# Power.net
KiCad netlist of a schematic drawn in Altium Designer
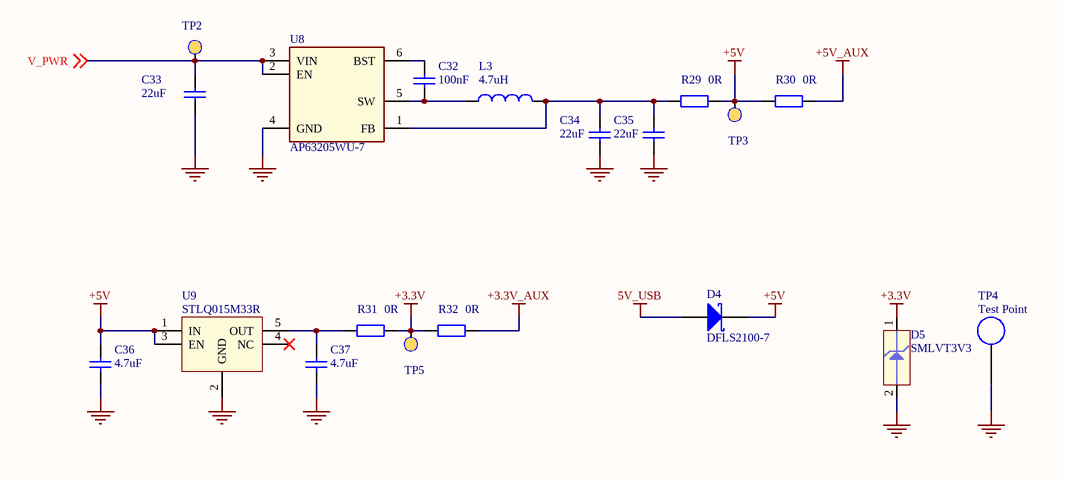
[diagram p0: Power.SchDoc]

(export (version "E")
  (design (tool "Eeschema 10.0.6"))
  (components
    (comp (ref "C32")
      (value "100nF")
      (footprint "C0402")
      (description "Capacitor ceramic")
      (fields
        (field (name "MANUFACTURER") "TDK Corporation")
        (field (name "MANUFACTURER PART NO.") "CGA2B3X7R1V104K050BB")
      )
      (libsource (lib "Miscellaneous Devices") (part "Cap Semi"))
    )
    (comp (ref "C33")
      (value "22uF")
      (footprint "C1210")
      (description "Capacitor ceramic")
      (fields
        (field (name "MANUFACTURER") "Taiyo Yuden")
        (field (name "MANUFACTURER PART NO.") "GMK325BJ226MM-P")
      )
      (libsource (lib "Miscellaneous Devices") (part "Cap Semi"))
    )
    (comp (ref "C34")
      (value "22uF")
      (footprint "C1210")
      (description "Capacitor ceramic")
      (fields
        (field (name "MANUFACTURER") "Taiyo Yuden")
        (field (name "MANUFACTURER PART NO.") "GMK325BJ226MM-P")
      )
      (libsource (lib "Miscellaneous Devices") (part "Cap Semi"))
    )
    (comp (ref "C35")
      (value "22uF")
      (footprint "C1210")
      (description "Capacitor ceramic")
      (fields
        (field (name "MANUFACTURER") "Taiyo Yuden")
        (field (name "MANUFACTURER PART NO.") "GMK325BJ226MM-P")
      )
      (libsource (lib "Miscellaneous Devices") (part "Cap Semi"))
    )
    (comp (ref "C36")
      (value "4.7uF")
      (footprint "C0805")
      (description "Capacitor ceramic")
      (fields
        (field (name "MANUFACTURER") "Murata Electronics")
        (field (name "MANUFACTURER PART NO.") "GRM219R6YA475KA73D")
      )
      (libsource (lib "Miscellaneous Devices") (part "Cap Semi"))
    )
    (comp (ref "C37")
      (value "4.7uF")
      (footprint "C0805")
      (description "Capacitor ceramic")
      (fields
        (field (name "MANUFACTURER") "Murata Electronics")
        (field (name "MANUFACTURER PART NO.") "GRM219R6YA475KA73D")
      )
      (libsource (lib "Miscellaneous Devices") (part "Cap Semi"))
    )
    (comp (ref "D4")
      (value "DFLS2100-7")
      (footprint "PowerDI123")
      (description "Schottky Diode")
      (fields (field (name "MANUFACTURER") "Diodes Incorporated"))
      (libsource (lib "Miscellaneous Devices") (part "D Schottky"))
    )
    (comp (ref "D5")
      (value "SMLVT3V3")
      (footprint "DO-214AA")
      (description "ESD Diode Symbol")
      (fields (field (name "MANUFACTURER") "STMicroelectronics"))
      (libsource (lib "ESD_Diode") (part "ESD_Diode"))
    )
    (comp (ref "L3")
      (value "4.7uH")
      (footprint "LQH3NP")
      (description "Inductor")
      (fields
        (field (name "MANUFACTURER") "Murata Electronics")
        (field (name "MANUFACTURER PART NO.") "LQH3NPN4R7MMEL")
      )
      (libsource (lib "Miscellaneous Devices") (part "Inductor"))
    )
    (comp (ref "R29")
      (value "0R")
      (footprint "R1206")
      (description "Resistor")
      (fields (field (name "MANUFACTURER") "Yageo") (field (name "MANUFACTURER PART NO.") "RC1206JR-070RL"))
      (libsource (lib "Miscellaneous Devices") (part "Res2"))
    )
    (comp (ref "R30")
      (value "0R")
      (footprint "R1206")
      (description "Resistor")
      (fields (field (name "MANUFACTURER") "Yageo") (field (name "MANUFACTURER PART NO.") "RC1206JR-070RL"))
      (libsource (lib "Miscellaneous Devices") (part "Res2"))
    )
    (comp (ref "R31")
      (value "0R")
      (footprint "R1206")
      (description "Resistor")
      (fields (field (name "MANUFACTURER") "Yageo") (field (name "MANUFACTURER PART NO.") "RC1206JR-070RL"))
      (libsource (lib "Miscellaneous Devices") (part "Res2"))
    )
    (comp (ref "R32")
      (value "0R")
      (footprint "R1206")
      (description "Resistor")
      (fields (field (name "MANUFACTURER") "Yageo") (field (name "MANUFACTURER PART NO.") "RC1206JR-070RL"))
      (libsource (lib "Miscellaneous Devices") (part "Res2"))
    )
    (comp (ref "TP2")
      (value "Test_Point")
      (footprint "TEST_POINT")
      (description "Test Point")
      (libsource (lib "Test Point") (part "Test_Point"))
    )
    (comp (ref "TP3")
      (value "Test_Point")
      (footprint "TEST_POINT")
      (description "Test Point")
      (libsource (lib "Test Point") (part "Test_Point"))
    )
    (comp (ref "TP4")
      (value "Test Point")
      (footprint "5019_keystone")
      (description "SMD Test Point")
      (fields
        (field (name "MANUFACTURER") "Keystone Electronics")
        (field (name "MANUFACTURER PART NO.") "5019")
      )
      (libsource (lib "test_point") (part "5019"))
    )
    (comp (ref "TP5")
      (value "Test_Point")
      (footprint "TEST_POINT")
      (description "Test Point")
      (libsource (lib "Test Point") (part "Test_Point"))
    )
    (comp (ref "U8")
      (value "AP63205WU-7")
      (footprint "SOT23-6_custom")
      (description "SYNCHRONOUS BUCK WITH ENHANCED EMI REDUCTION")
      (fields (field (name "MANUFACTURER") "Diodes Incorporated"))
      (libsource (lib "AP63205WU-7") (part "AP63205WU-7"))
    )
    (comp (ref "U9")
      (value "STLQ015M33R")
      (footprint "SOT23-5L")
      (description "Ultra low quiescent current linear voltage regulator")
      (fields (field (name "MANUFACTURER") "STMicroelectronics"))
      (libsource (lib "STLQ015M33R") (part "STLQ015M33R"))
    )
  )
  (nets
    (net (code "1") (name "+3.3V") (class "Default")
      (node (ref "D5") (pin "1") (pinfunction "PIN1_1") (pintype "passive"))
      (node (ref "R31") (pin "1") (pinfunction "1_1") (pintype "passive"))
      (node (ref "R32") (pin "2") (pinfunction "2_2") (pintype "passive"))
      (node (ref "TP5") (pin "0") (pinfunction "0_0") (pintype "passive"))
    )
    (net (code "2") (name "+3.3V_AUX") (class "Default")
      (node (ref "R32") (pin "1") (pinfunction "1_1") (pintype "passive"))
    )
    (net (code "3") (name "+5V") (class "Default")
      (node (ref "C36") (pin "2") (pinfunction "2_2") (pintype "passive"))
      (node (ref "D4") (pin "2") (pinfunction "K_2") (pintype "passive"))
      (node (ref "R29") (pin "1") (pinfunction "1_1") (pintype "passive"))
      (node (ref "R30") (pin "2") (pinfunction "2_2") (pintype "passive"))
      (node (ref "TP3") (pin "0") (pinfunction "0_0") (pintype "passive"))
      (node (ref "U9") (pin "1") (pinfunction "IN_1") (pintype "passive"))
      (node (ref "U9") (pin "3") (pinfunction "EN_3") (pintype "passive"))
    )
    (net (code "4") (name "+5V_AUX") (class "Default")
      (node (ref "R30") (pin "1") (pinfunction "1_1") (pintype "passive"))
    )
    (net (code "5") (name "5V_USB") (class "Default")
      (node (ref "D4") (pin "1") (pinfunction "A_1") (pintype "passive"))
    )
    (net (code "6") (name "GND") (class "Default")
      (node (ref "C33") (pin "1") (pinfunction "1_1") (pintype "passive"))
      (node (ref "C34") (pin "1") (pinfunction "1_1") (pintype "passive"))
      (node (ref "C35") (pin "1") (pinfunction "1_1") (pintype "passive"))
      (node (ref "C36") (pin "1") (pinfunction "1_1") (pintype "passive"))
      (node (ref "C37") (pin "1") (pinfunction "1_1") (pintype "passive"))
      (node (ref "D5") (pin "2") (pinfunction "PIN2_2") (pintype "passive"))
      (node (ref "TP4") (pin "1") (pinfunction "1_1") (pintype "passive"))
      (node (ref "U8") (pin "4") (pinfunction "GND_4") (pintype "passive"))
      (node (ref "U9") (pin "2") (pinfunction "GND_2") (pintype "passive"))
    )
    (net (code "7") (name "Net-(U8-BST)") (class "Default")
      (node (ref "C32") (pin "2") (pinfunction "2_2") (pintype "passive"))
      (node (ref "U8") (pin "6") (pinfunction "BST_6") (pintype "passive"))
    )
    (net (code "8") (name "Net-(U8-FB)") (class "Default")
      (node (ref "C34") (pin "2") (pinfunction "2_2") (pintype "passive"))
      (node (ref "C35") (pin "2") (pinfunction "2_2") (pintype "passive"))
      (node (ref "L3") (pin "2") (pinfunction "2_2") (pintype "passive"))
      (node (ref "R29") (pin "2") (pinfunction "2_2") (pintype "passive"))
      (node (ref "U8") (pin "1") (pinfunction "FB_1") (pintype "passive"))
    )
    (net (code "9") (name "Net-(U8-SW)") (class "Default")
      (node (ref "C32") (pin "1") (pinfunction "1_1") (pintype "passive"))
      (node (ref "L3") (pin "1") (pinfunction "1_1") (pintype "passive"))
      (node (ref "U8") (pin "5") (pinfunction "SW_5") (pintype "passive"))
    )
    (net (code "10") (name "Net-(U9-OUT)") (class "Default")
      (node (ref "C37") (pin "2") (pinfunction "2_2") (pintype "passive"))
      (node (ref "R31") (pin "2") (pinfunction "2_2") (pintype "passive"))
      (node (ref "U9") (pin "5") (pinfunction "OUT_5") (pintype "passive"))
    )
    (net (code "11") (name "V_PWR") (class "Default")
      (node (ref "C33") (pin "2") (pinfunction "2_2") (pintype "passive"))
      (node (ref "TP2") (pin "0") (pinfunction "0_0") (pintype "passive"))
      (node (ref "U8") (pin "2") (pinfunction "EN_2") (pintype "passive"))
      (node (ref "U8") (pin "3") (pinfunction "VIN_3") (pintype "passive"))
    )
    (net (code "12") (name "unconnected-(U9-NC-Pad4)") (class "Default")
      (node (ref "U9") (pin "4") (pinfunction "NC_4") (pintype "passive+no_connect"))
    )
  )
)
